# charLED4inchess.net
KiCad netlist of a schematic drawn in EAGLE
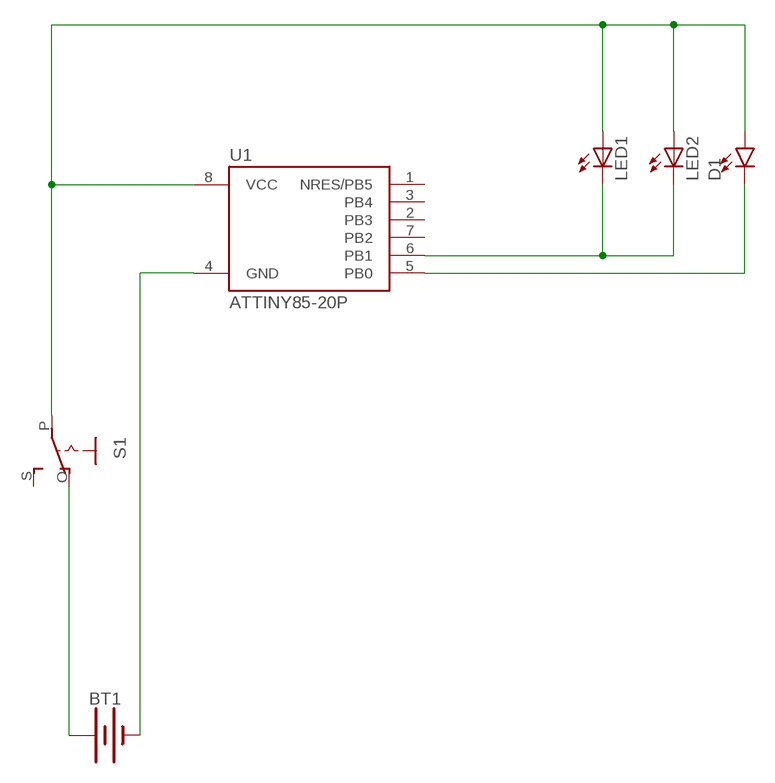
[diagram p0: schematic, sheet 1]

(export (version "E")
  (design (tool "Eeschema 10.0.6"))
  (components
    (comp (ref "BT1")
      (value "BATTERY-20MM_PTH")
      (footprint "eagle-import:BATTCOM_20MM_PTH")
      (libsource (lib "eagle-import") (part "BATTERY-20MM_PTH"))
    )
    (comp (ref "D1")
      (value "LED3MM")
      (footprint "eagle-import:LED_3MM")
      (libsource (lib "eagle-import") (part "LED3MM"))
    )
    (comp (ref "LED1")
      (value "LED5MM")
      (footprint "eagle-import:LED5MM")
      (libsource (lib "eagle-import") (part "adafruit_LED5MM"))
    )
    (comp (ref "LED2")
      (value "LED5MM")
      (footprint "eagle-import:LED5MM")
      (libsource (lib "eagle-import") (part "adafruit_LED5MM"))
    )
    (comp (ref "S1")
      (value "EG1218S")
      (footprint "eagle-import:EG1218")
      (libsource (lib "eagle-import") (part "EG1218S"))
    )
    (comp (ref "U1")
      (value "ATTINY85-20P")
      (footprint "eagle-import:PDIP08_300MIL")
      (libsource (lib "eagle-import") (part "ATTINY85P-20"))
    )
  )
  (nets
    (net (code "1") (name "Net-(BT1-+)") (class "Default")
      (node (ref "BT1") (pin "1") (pinfunction "+_1") (pintype "power_in"))
      (node (ref "S1") (pin "O") (pinfunction "O_O") (pintype "passive"))
    )
    (net (code "2") (name "Net-(BT1--)") (class "Default")
      (node (ref "BT1") (pin "2") (pinfunction "-_2") (pintype "power_in"))
      (node (ref "U1") (pin "4") (pinfunction "GND_4") (pintype "power_in"))
    )
    (net (code "3") (name "Net-(D1-C)") (class "Default")
      (node (ref "D1") (pin "K") (pinfunction "C_K") (pintype "passive"))
      (node (ref "U1") (pin "5") (pinfunction "PB0_5") (pintype "bidirectional"))
    )
    (net (code "4") (name "Net-(LED1-C)") (class "Default")
      (node (ref "LED1") (pin "K") (pinfunction "C_K") (pintype "passive"))
      (node (ref "LED2") (pin "K") (pinfunction "C_K") (pintype "passive"))
      (node (ref "U1") (pin "6") (pinfunction "PB1_6") (pintype "bidirectional"))
    )
    (net (code "5") (name "Net-(U1-VCC)") (class "Default")
      (node (ref "D1") (pin "A") (pinfunction "A_A") (pintype "passive"))
      (node (ref "LED1") (pin "A") (pinfunction "A_A") (pintype "passive"))
      (node (ref "LED2") (pin "A") (pinfunction "A_A") (pintype "passive"))
      (node (ref "S1") (pin "P") (pinfunction "P_P") (pintype "passive"))
      (node (ref "U1") (pin "8") (pinfunction "VCC_8") (pintype "power_in"))
    )
    (net (code "6") (name "unconnected-(S1-PadS)") (class "Default")
      (node (ref "S1") (pin "S") (pinfunction "S_S") (pintype "passive"))
    )
    (net (code "7") (name "unconnected-(U1-NRES{slash}PB5-Pad1)") (class "Default")
      (node (ref "U1") (pin "1") (pinfunction "NRES/PB5_1") (pintype "bidirectional"))
    )
    (net (code "8") (name "unconnected-(U1-PB2-Pad7)") (class "Default")
      (node (ref "U1") (pin "7") (pinfunction "PB2_7") (pintype "bidirectional"))
    )
    (net (code "9") (name "unconnected-(U1-PB3-Pad2)") (class "Default")
      (node (ref "U1") (pin "2") (pinfunction "PB3_2") (pintype "bidirectional"))
    )
    (net (code "10") (name "unconnected-(U1-PB4-Pad3)") (class "Default")
      (node (ref "U1") (pin "3") (pinfunction "PB4_3") (pintype "bidirectional"))
    )
  )
)
